# DSV1-001_V2.net
KiCad netlist of a schematic drawn in Altium Designer
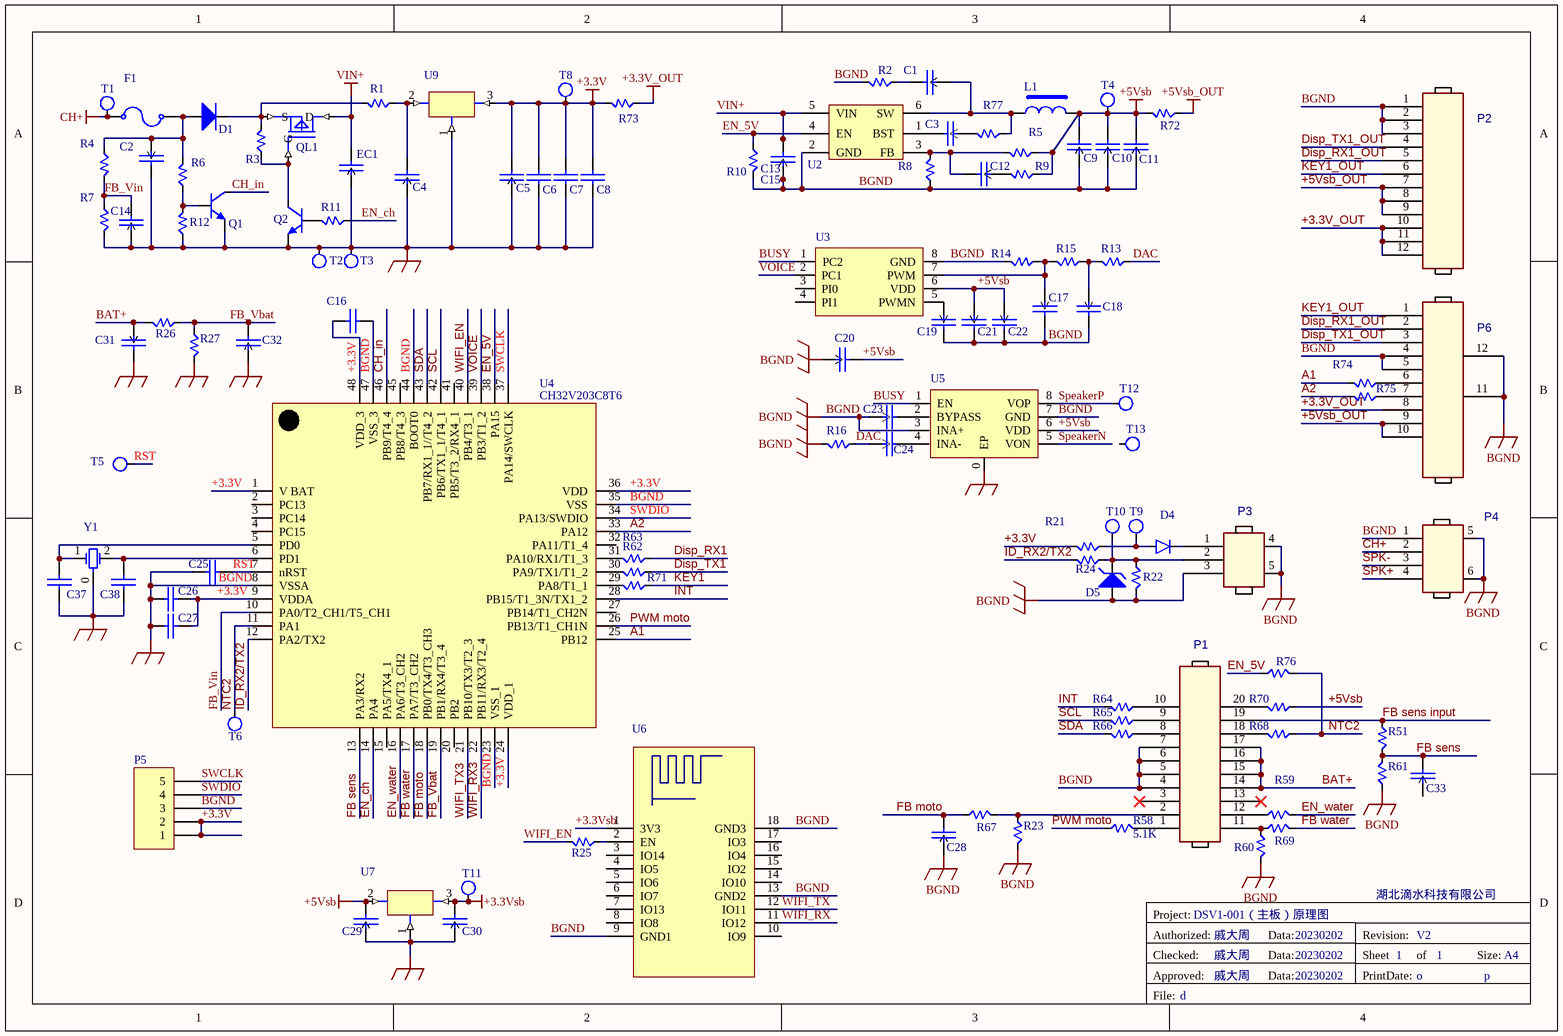
[diagram p0: DSV1-001（主板）原理图 V2.SchDoc]

(export (version "E")
  (design (tool "Eeschema 10.0.6"))
  (components
    (comp (ref "C1")
      (value "102")
      (footprint "0603C")
      (description "Capacitor")
      (libsource (lib "*") (part "CAP"))
    )
    (comp (ref "C2")
      (value "104")
      (footprint "0603C")
      (description "Capacitor")
      (libsource (lib "*") (part "CAP"))
    )
    (comp (ref "C3")
      (value "104")
      (footprint "0603C")
      (description "Capacitor")
      (libsource (lib "*") (part "CAP"))
    )
    (comp (ref "C4")
      (value "104")
      (footprint "0603C")
      (description "Capacitor")
      (libsource (lib "*") (part "CAP"))
    )
    (comp (ref "C5")
      (value "226")
      (footprint "0603C")
      (description "Capacitor")
      (libsource (lib "*") (part "CAP"))
    )
    (comp (ref "C6") (value "226") (footprint "0603c") (libsource (lib "") (part "CAP_1")))
    (comp (ref "C7") (value "103") (footprint "0603c") (libsource (lib "") (part "CAP_1")))
    (comp (ref "C8") (value "104") (footprint "0603c") (libsource (lib "") (part "CAP_1")))
    (comp (ref "C9")
      (value "226")
      (footprint "0603C")
      (description "Capacitor")
      (libsource (lib "*") (part "CAP"))
    )
    (comp (ref "C10")
      (value "226")
      (footprint "0603C")
      (description "Capacitor")
      (libsource (lib "*") (part "CAP"))
    )
    (comp (ref "C11")
      (value "104")
      (footprint "0603C")
      (description "Capacitor")
      (libsource (lib "*") (part "CAP"))
    )
    (comp (ref "C12")
      (value "101")
      (footprint "0603C")
      (description "Capacitor")
      (libsource (lib "*") (part "CAP"))
    )
    (comp (ref "C13")
      (value "104")
      (footprint "0603C")
      (description "Capacitor")
      (libsource (lib "*") (part "CAP"))
    )
    (comp (ref "C14")
      (value "104")
      (footprint "0603C")
      (description "Capacitor")
      (libsource (lib "*") (part "CAP"))
    )
    (comp (ref "C15")
      (value "104")
      (footprint "0603C")
      (description "Capacitor")
      (libsource (lib "*") (part "CAP"))
    )
    (comp (ref "C16") (value "103") (footprint "0603c") (libsource (lib "") (part "CAP_1")))
    (comp (ref "C17")
      (value "102")
      (footprint "0603C")
      (description "Capacitor")
      (libsource (lib "*") (part "CAP"))
    )
    (comp (ref "C18")
      (value "102")
      (footprint "0603C")
      (description "Capacitor")
      (libsource (lib "*") (part "CAP"))
    )
    (comp (ref "C19")
      (value "102")
      (footprint "0603C")
      (description "Capacitor")
      (libsource (lib "*") (part "CAP"))
    )
    (comp (ref "C20")
      (value "104")
      (footprint "0603C")
      (description "Capacitor")
      (libsource (lib "*") (part "CAP"))
    )
    (comp (ref "C21")
      (value "105")
      (footprint "0805C")
      (description "Capacitor")
      (libsource (lib "*") (part "CAP"))
    )
    (comp (ref "C22")
      (value "226")
      (footprint "0805C")
      (description "Capacitor")
      (libsource (lib "*") (part "CAP"))
    )
    (comp (ref "C23")
      (value "105")
      (footprint "0603C")
      (description "Capacitor")
      (libsource (lib "*") (part "CAP"))
    )
    (comp (ref "C24")
      (value "104")
      (footprint "0603C")
      (description "Capacitor")
      (libsource (lib "*") (part "CAP"))
    )
    (comp (ref "C25") (value "103") (footprint "0603c") (libsource (lib "") (part "CAP_1")))
    (comp (ref "C26") (value "104") (footprint "0603c") (libsource (lib "") (part "CAP_1")))
    (comp (ref "C27") (value "105") (footprint "0603c") (libsource (lib "") (part "CAP_1")))
    (comp (ref "C28")
      (value "104")
      (footprint "0603C")
      (description "Capacitor")
      (libsource (lib "*") (part "CAP"))
    )
    (comp (ref "C29")
      (value "NC")
      (footprint "0603c")
      (description "Capacitor")
      (libsource (lib "*") (part "CAP"))
    )
    (comp (ref "C30")
      (value "NC")
      (footprint "0603c")
      (description "Capacitor")
      (libsource (lib "*") (part "CAP"))
    )
    (comp (ref "C31")
      (value "104")
      (footprint "0603C")
      (description "Capacitor")
      (libsource (lib "*") (part "CAP"))
    )
    (comp (ref "C32")
      (value "104")
      (footprint "0603C")
      (description "Capacitor")
      (libsource (lib "*") (part "CAP"))
    )
    (comp (ref "C33")
      (value "104")
      (footprint "0603C")
      (description "Capacitor")
      (libsource (lib "*") (part "CAP"))
    )
    (comp (ref "C37") (value "12P") (footprint "0603c") (libsource (lib "") (part "CAP_1")))
    (comp (ref "C38") (value "12P") (footprint "0603c") (libsource (lib "") (part "CAP_1")))
    (comp (ref "D1")
      (value "SS54L")
      (footprint "SMB-A")
      (description "High Conductance Fast Diode")
      (libsource (lib "Miscellaneous Devices") (part "Diode 1N4448"))
    )
    (comp (ref "D4") (value "LMBR340") (footprint "SOD-123") (libsource (lib "我的元件库") (part "1N4148")))
    (comp (ref "D5")
      (value "TVS3.3V")
      (footprint "SOD-123")
      (description "Zener Diode")
      (libsource (lib "Miscellaneous Devices") (part "D Zener"))
    )
    (comp (ref "EC1")
      (value "476")
      (footprint "1210-c")
      (description "Capacitor")
      (libsource (lib "*") (part "CAP"))
    )
    (comp (ref "F1")
      (value "1200mA/24V")
      (footprint "1206-R")
      (description "Fuse")
      (libsource (lib "我的元件库") (part "FUSe-a"))
    )
    (comp (ref "L1") (value "4R7") (footprint "CLD-54") (libsource (lib "我的元件库") (part "电感")))
    (comp (ref "P1")
      (value "SGDBM-08-020P-H70")
      (footprint "SGDBM_08_020P_H40")
      (libsource (lib "*") (part "HEADER 12_1"))
    )
    (comp (ref "P2")
      (value "SGDBM-08-012P-H70")
      (footprint "SGDBM_08_012P_H40")
      (libsource (lib "*") (part "HEADER 12_0"))
    )
    (comp (ref "P3")
      (value "HEADER 3")
      (footprint "con125_03_wt_thw")
      (libsource (lib "*") (part "HEADER 3_1"))
    )
    (comp (ref "P4")
      (value "BC-60-4P300-C06")
      (footprint "BC_60_4P_C06")
      (libsource (lib "*") (part "HEADER 4_1"))
    )
    (comp (ref "P5")
      (value "~")
      (footprint "2.0-5 顶针焊盘")
      (description "Header, 5-Pin")
      (libsource (lib "Miscellaneous Connectors") (part "Header 5"))
    )
    (comp (ref "P6")
      (value "HC 0.8 10PWT")
      (footprint "HC_08_10PWT")
      (libsource (lib "*") (part "HEADER 12_2"))
    )
    (comp (ref "Q1")
      (value "MMBT2222A")
      (footprint "SOT-23-ss")
      (description "NPN General Purpose Amplifier")
      (libsource (lib "altium-import") (part "root_0__Miscellaneous Devices.IntLib"))
    )
    (comp (ref "Q2")
      (value "MMBT2222A")
      (footprint "SOT-23-ss")
      (description "NPN General Purpose Amplifier")
      (libsource (lib "altium-import") (part "root_0_mirrored__Miscellaneous Devices.IntLib"))
    )
    (comp (ref "QL1") (value "MOS-P") (footprint "SOT-23-MOS-N") (libsource (lib "Easen liu") (part "MOS-P")))
    (comp (ref "R1") (value "100R/0805") (footprint "0603R") (libsource (lib "*") (part "电阻 - R")))
    (comp (ref "R2") (value "22R") (footprint "0603R") (libsource (lib "*") (part "电阻 - R")))
    (comp (ref "R3") (value "510K") (footprint "0603r") (libsource (lib "*") (part "电阻 - R")))
    (comp (ref "R4") (value "10K") (footprint "0805R") (libsource (lib "*") (part "电阻 - R")))
    (comp (ref "R5") (value "68K") (footprint "0603R") (libsource (lib "*") (part "电阻 - R")))
    (comp (ref "R6") (value "100K") (footprint "0603R") (libsource (lib "*") (part "电阻 - R")))
    (comp (ref "R7") (value "1.6K") (footprint "0805r") (libsource (lib "*") (part "电阻 - R")))
    (comp (ref "R8") (value "9.1K") (footprint "0603R") (libsource (lib "*") (part "电阻 - R")))
    (comp (ref "R9") (value "2K") (footprint "0603R") (libsource (lib "*") (part "电阻 - R")))
    (comp (ref "R10") (value "100K") (footprint "0603R") (libsource (lib "*") (part "电阻 - R")))
    (comp (ref "R11") (value "5.1K") (footprint "0603R") (libsource (lib "*") (part "电阻 - R")))
    (comp (ref "R12") (value "10K") (footprint "0603R") (libsource (lib "*") (part "电阻 - R")))
    (comp (ref "R13") (value "10K") (footprint "0603R") (libsource (lib "*") (part "电阻 - R")))
    (comp (ref "R14") (value "470R") (footprint "0603R") (libsource (lib "*") (part "电阻 - R")))
    (comp (ref "R15") (value "4.7K") (footprint "0603R") (libsource (lib "*") (part "电阻 - R")))
    (comp (ref "R16") (value "2K") (footprint "0603R") (libsource (lib "*") (part "电阻 - R")))
    (comp (ref "R21") (value "16V/50mA") (footprint "0603r") (libsource (lib "*") (part "电阻 - R")))
    (comp (ref "R22") (value "1M") (footprint "0603R") (libsource (lib "*") (part "电阻 - R")))
    (comp (ref "R23") (value "10K") (footprint "0603R") (libsource (lib "*") (part "电阻 - R")))
    (comp (ref "R24") (value "1K") (footprint "0603r") (libsource (lib "*") (part "电阻 - R")))
    (comp (ref "R25") (value "NC") (footprint "0603r") (libsource (lib "*") (part "电阻 - R")))
    (comp (ref "R26") (value "10M") (footprint "0603r") (libsource (lib "*") (part "电阻 - R")))
    (comp (ref "R27") (value "1.6M") (footprint "0603r") (libsource (lib "*") (part "电阻 - R")))
    (comp (ref "R51") (value "5.1K") (footprint "0603R") (libsource (lib "*") (part "电阻 - R")))
    (comp (ref "R58") (value "5.1K") (footprint "0603R") (libsource (lib "*") (part "电阻 - R")))
    (comp (ref "R59") (value "5.1K") (footprint "0603R") (libsource (lib "*") (part "电阻 - R")))
    (comp (ref "R60") (value "10K") (footprint "0603R") (libsource (lib "*") (part "电阻 - R")))
    (comp (ref "R61") (value "10K") (footprint "0603R") (libsource (lib "*") (part "电阻 - R")))
    (comp (ref "R62") (value "100R") (footprint "0603R") (libsource (lib "*") (part "电阻 - R")))
    (comp (ref "R63") (value "100R") (footprint "0603R") (libsource (lib "*") (part "电阻 - R")))
    (comp (ref "R64") (value "100R") (footprint "0603R") (libsource (lib "*") (part "电阻 - R")))
    (comp (ref "R65") (value "100R") (footprint "0603R") (libsource (lib "*") (part "电阻 - R")))
    (comp (ref "R66") (value "100R") (footprint "0603R") (libsource (lib "*") (part "电阻 - R")))
    (comp (ref "R67") (value "1K") (footprint "0603R") (libsource (lib "*") (part "电阻 - R")))
    (comp (ref "R68") (value "100R") (footprint "0603R") (libsource (lib "*") (part "电阻 - R")))
    (comp (ref "R69") (value "1K") (footprint "0603R") (libsource (lib "*") (part "电阻 - R")))
    (comp (ref "R70") (value "33R") (footprint "0603R") (libsource (lib "*") (part "电阻 - R")))
    (comp (ref "R71") (value "1K") (footprint "0603R") (libsource (lib "*") (part "电阻 - R")))
    (comp (ref "R72") (value "0R") (footprint "0603R") (libsource (lib "*") (part "电阻 - R")))
    (comp (ref "R73") (value "33R") (footprint "0603R") (libsource (lib "*") (part "电阻 - R")))
    (comp (ref "R74") (value "100R") (footprint "0603R") (libsource (lib "*") (part "电阻 - R")))
    (comp (ref "R75") (value "100R") (footprint "0603R") (libsource (lib "*") (part "电阻 - R")))
    (comp (ref "R76") (value "10K") (footprint "0603R") (libsource (lib "*") (part "电阻 - R")))
    (comp (ref "R77") (value "0R") (footprint "0603R") (libsource (lib "*") (part "电阻 - R")))
    (comp (ref "T1") (value "~") (footprint "TP") (libsource (lib "*") (part "TP")))
    (comp (ref "T2") (value "~") (footprint "TP") (libsource (lib "*") (part "TP")))
    (comp (ref "T3") (value "~") (footprint "TP") (libsource (lib "*") (part "TP")))
    (comp (ref "T4") (value "~") (footprint "TP") (libsource (lib "*") (part "TP")))
    (comp (ref "T5") (value "~") (footprint "TP") (libsource (lib "*") (part "TP")))
    (comp (ref "T6") (value "~") (footprint "TP") (libsource (lib "*") (part "TP")))
    (comp (ref "T8") (value "~") (footprint "TP") (libsource (lib "*") (part "TP")))
    (comp (ref "T9") (value "~") (footprint "TP") (libsource (lib "*") (part "TP")))
    (comp (ref "T10") (value "~") (footprint "TP") (libsource (lib "*") (part "TP")))
    (comp (ref "T11") (value "~") (footprint "TP") (libsource (lib "*") (part "TP")))
    (comp (ref "T12") (value "~") (footprint "TP") (libsource (lib "*") (part "TP")))
    (comp (ref "T13") (value "~") (footprint "TP") (libsource (lib "*") (part "TP")))
    (comp (ref "U2")
      (value "JW5057S")
      (footprint "SOT23-6-T")
      (description "Header, 6-Pin")
      (libsource (lib "我的元件库") (part "Header 6"))
    )
    (comp (ref "U3")
      (value "FT61F141-RB")
      (footprint "SOP-8 xiao")
      (description "62 Pin EISA Connector")
      (libsource (lib "我的元件库") (part "IC SOT-8"))
    )
    (comp (ref "U4") (value "CH32V203C8T6") (footprint "LQFP-48") (libsource (lib "我的元件库") (part "MM32F031")))
    (comp (ref "U5")
      (value "FT61F141-RB")
      (footprint "SOP-8-0")
      (description "62 Pin EISA Connector")
      (libsource (lib "") (part "IC SOT-8_1"))
    )
    (comp (ref "U6") (value "HI3861") (footprint "ESP8266") (libsource (lib "我的元件库") (part "ESP8266")))
    (comp (ref "U7") (value "LD1117AGC33") (footprint "SOT-89") (libsource (lib "Easen liu") (part "ME6203")))
    (comp (ref "U9")
      (value "ME6239A33M3G")
      (footprint "SOT-89")
      (libsource (lib "Easen liu") (part "ME6203"))
    )
    (comp (ref "Y1") (value "8M") (footprint "3225 XTAL") (libsource (lib "我的元件库") (part "XTAL")))
  )
  (nets
    (net (code "1") (name "+3.3V") (class "Default")
      (node (ref "C16") (pin "2") (pinfunction "2_2") (pintype "passive"))
      (node (ref "C26") (pin "1") (pinfunction "1_1") (pintype "passive"))
      (node (ref "C27") (pin "1") (pinfunction "1_1") (pintype "passive"))
      (node (ref "C5") (pin "2") (pinfunction "2_2") (pintype "passive"))
      (node (ref "C6") (pin "1") (pinfunction "1_1") (pintype "passive"))
      (node (ref "C7") (pin "1") (pinfunction "1_1") (pintype "passive"))
      (node (ref "C8") (pin "1") (pinfunction "1_1") (pintype "passive"))
      (node (ref "P5") (pin "1") (pinfunction "1_1") (pintype "passive"))
      (node (ref "P5") (pin "2") (pinfunction "2_2") (pintype "passive"))
      (node (ref "R21") (pin "2") (pinfunction "2_2") (pintype "passive"))
      (node (ref "R73") (pin "2") (pinfunction "2_2") (pintype "passive"))
      (node (ref "T8") (pin "1") (pinfunction "1_1") (pintype "passive"))
      (node (ref "U4") (pin "1") (pinfunction "V_BAT_1") (pintype "passive"))
      (node (ref "U4") (pin "24") (pinfunction "VDD_1_24") (pintype "passive"))
      (node (ref "U4") (pin "36") (pinfunction "VDD_36") (pintype "passive"))
      (node (ref "U4") (pin "48") (pinfunction "VDD_3_48") (pintype "passive"))
      (node (ref "U4") (pin "9") (pinfunction "VDDA_9") (pintype "passive"))
      (node (ref "U9") (pin "3") (pinfunction "3_3") (pintype "input"))
    )
    (net (code "2") (name "+3.3V_OUT") (class "Default")
      (node (ref "P2") (pin "10") (pinfunction "10_10") (pintype "passive"))
      (node (ref "P2") (pin "11") (pinfunction "11_11") (pintype "passive"))
      (node (ref "P2") (pin "12") (pinfunction "12_12") (pintype "passive"))
      (node (ref "P6") (pin "8") (pinfunction "8_8") (pintype "passive"))
      (node (ref "R73") (pin "1") (pinfunction "1_1") (pintype "passive"))
    )
    (net (code "3") (name "+3.3Vsb") (class "Default")
      (node (ref "C30") (pin "2") (pinfunction "2_2") (pintype "passive"))
      (node (ref "T11") (pin "1") (pinfunction "1_1") (pintype "passive"))
      (node (ref "U6") (pin "1") (pinfunction "3V3_1") (pintype "open_emitter"))
      (node (ref "U7") (pin "3") (pinfunction "3_3") (pintype "input"))
    )
    (net (code "4") (name "+5Vsb") (class "Default")
      (node (ref "C10") (pin "2") (pinfunction "2_2") (pintype "passive"))
      (node (ref "C11") (pin "2") (pinfunction "2_2") (pintype "passive"))
      (node (ref "C20") (pin "2") (pinfunction "2_2") (pintype "passive"))
      (node (ref "C21") (pin "1") (pinfunction "1_1") (pintype "passive"))
      (node (ref "C22") (pin "1") (pinfunction "1_1") (pintype "passive"))
      (node (ref "C29") (pin "2") (pinfunction "2_2") (pintype "passive"))
      (node (ref "C9") (pin "2") (pinfunction "2_2") (pintype "passive"))
      (node (ref "L1") (pin "2") (pinfunction "2_2") (pintype "passive"))
      (node (ref "R5") (pin "1") (pinfunction "1_1") (pintype "passive"))
      (node (ref "R70") (pin "2") (pinfunction "2_2") (pintype "passive"))
      (node (ref "R72") (pin "2") (pinfunction "2_2") (pintype "passive"))
      (node (ref "R9") (pin "1") (pinfunction "1_1") (pintype "passive"))
      (node (ref "T4") (pin "1") (pinfunction "1_1") (pintype "passive"))
      (node (ref "U3") (pin "6") (pinfunction "VDD_6") (pintype "passive"))
      (node (ref "U5") (pin "6") (pinfunction "VDD_6") (pintype "passive"))
      (node (ref "U7") (pin "2") (pinfunction "2_2") (pintype "input"))
    )
    (net (code "5") (name "+5Vsb_OUT") (class "Default")
      (node (ref "P2") (pin "7") (pinfunction "7_7") (pintype "passive"))
      (node (ref "P2") (pin "8") (pinfunction "8_8") (pintype "passive"))
      (node (ref "P2") (pin "9") (pinfunction "9_9") (pintype "passive"))
      (node (ref "P6") (pin "10") (pinfunction "10_10") (pintype "passive"))
      (node (ref "P6") (pin "9") (pinfunction "9_9") (pintype "passive"))
      (node (ref "R72") (pin "1") (pinfunction "1_1") (pintype "passive"))
    )
    (net (code "6") (name "/A1") (class "Default")
      (node (ref "R74") (pin "2") (pinfunction "2_2") (pintype "passive"))
      (node (ref "U4") (pin "25") (pinfunction "PB12_25") (pintype "passive"))
    )
    (net (code "7") (name "/A2") (class "Default")
      (node (ref "R75") (pin "2") (pinfunction "2_2") (pintype "passive"))
      (node (ref "U4") (pin "33") (pinfunction "PA12_33") (pintype "passive"))
    )
    (net (code "8") (name "/BAT+") (class "Default")
      (node (ref "C31") (pin "1") (pinfunction "1_1") (pintype "passive"))
      (node (ref "P1") (pin "14") (pinfunction "14_14") (pintype "passive"))
      (node (ref "P1") (pin "15") (pinfunction "15_15") (pintype "passive"))
      (node (ref "P1") (pin "16") (pinfunction "16_16") (pintype "passive"))
      (node (ref "P1") (pin "17") (pinfunction "17_17") (pintype "passive"))
      (node (ref "R26") (pin "1") (pinfunction "1_1") (pintype "passive"))
    )
    (net (code "9") (name "/BUSY") (class "Default")
      (node (ref "U3") (pin "1") (pinfunction "PC2_1") (pintype "power_in"))
      (node (ref "U5") (pin "1") (pinfunction "EN_1") (pintype "power_in"))
    )
    (net (code "10") (name "/CH_in") (class "Default")
      (node (ref "Q1") (pin "3") (pinfunction "3_3") (pintype "passive"))
      (node (ref "U4") (pin "46") (pinfunction "PB9/T4_4_46") (pintype "passive"))
    )
    (net (code "11") (name "/DAC") (class "Default")
      (node (ref "C24") (pin "1") (pinfunction "1_1") (pintype "passive"))
      (node (ref "R13") (pin "2") (pinfunction "2_2") (pintype "passive"))
      (node (ref "R16") (pin "2") (pinfunction "2_2") (pintype "passive"))
    )
    (net (code "12") (name "/Disp_RX1") (class "Default")
      (node (ref "R63") (pin "2") (pinfunction "2_2") (pintype "passive"))
    )
    (net (code "13") (name "/Disp_RX1_OUT") (class "Default")
      (node (ref "P2") (pin "5") (pinfunction "5_5") (pintype "passive"))
      (node (ref "P6") (pin "2") (pinfunction "2_2") (pintype "passive"))
    )
    (net (code "14") (name "/Disp_TX1") (class "Default")
      (node (ref "R62") (pin "2") (pinfunction "2_2") (pintype "passive"))
    )
    (net (code "15") (name "/Disp_TX1_OUT") (class "Default")
      (node (ref "P2") (pin "4") (pinfunction "4_4") (pintype "passive"))
      (node (ref "P6") (pin "3") (pinfunction "3_3") (pintype "passive"))
    )
    (net (code "16") (name "/EN_5V") (class "Default")
      (node (ref "R10") (pin "1") (pinfunction "1_1") (pintype "passive"))
      (node (ref "R76") (pin "2") (pinfunction "2_2") (pintype "passive"))
      (node (ref "U2") (pin "4") (pinfunction "EN_4") (pintype "passive"))
      (node (ref "U4") (pin "38") (pinfunction "PA15_38") (pintype "passive"))
    )
    (net (code "17") (name "/EN_ch") (class "Default")
      (node (ref "R11") (pin "1") (pinfunction "1_1") (pintype "passive"))
      (node (ref "U4") (pin "14") (pinfunction "PA4_14") (pintype "passive"))
    )
    (net (code "18") (name "/EN_water") (class "Default")
      (node (ref "R59") (pin "1") (pinfunction "1_1") (pintype "passive"))
      (node (ref "U4") (pin "16") (pinfunction "PA6/T3_CH2_16") (pintype "passive"))
    )
    (net (code "19") (name "/FB moto") (class "Default")
      (node (ref "C28") (pin "2") (pinfunction "2_2") (pintype "passive"))
      (node (ref "R67") (pin "2") (pinfunction "2_2") (pintype "passive"))
      (node (ref "U4") (pin "18") (pinfunction "PB0/TX4/T3_CH3_18") (pintype "passive"))
    )
    (net (code "20") (name "/FB sens") (class "Default")
      (node (ref "C33") (pin "2") (pinfunction "2_2") (pintype "passive"))
      (node (ref "R51") (pin "1") (pinfunction "1_1") (pintype "passive"))
      (node (ref "R61") (pin "1") (pinfunction "1_1") (pintype "passive"))
      (node (ref "U4") (pin "13") (pinfunction "PA3/RX2_13") (pintype "passive"))
    )
    (net (code "21") (name "/FB sens input") (class "Default")
      (node (ref "P1") (pin "19") (pinfunction "19_19") (pintype "passive"))
      (node (ref "R51") (pin "2") (pinfunction "2_2") (pintype "passive"))
    )
    (net (code "22") (name "/FB water") (class "Default")
      (node (ref "R69") (pin "1") (pinfunction "1_1") (pintype "passive"))
      (node (ref "U4") (pin "17") (pinfunction "PA7/T3_CH2_17") (pintype "passive"))
    )
    (net (code "23") (name "/FB_Vbat") (class "Default")
      (node (ref "C32") (pin "2") (pinfunction "2_2") (pintype "passive"))
      (node (ref "R26") (pin "2") (pinfunction "2_2") (pintype "passive"))
      (node (ref "R27") (pin "2") (pinfunction "2_2") (pintype "passive"))
      (node (ref "U4") (pin "19") (pinfunction "PB1/RX4/T3_4_19") (pintype "passive"))
    )
    (net (code "24") (name "/FB_Vin") (class "Default")
      (node (ref "C14") (pin "2") (pinfunction "2_2") (pintype "passive"))
      (node (ref "R4") (pin "2") (pinfunction "2_2") (pintype "passive"))
      (node (ref "R7") (pin "2") (pinfunction "2_2") (pintype "passive"))
      (node (ref "U4") (pin "10") (pinfunction "PA0/T2_CH1/T5_CH1_10") (pintype "passive"))
    )
    (net (code "25") (name "/ID_RX2{slash}TX2") (class "Default")
      (node (ref "R24") (pin "2") (pinfunction "2_2") (pintype "passive"))
      (node (ref "U4") (pin "12") (pinfunction "PA2/TX2_12") (pintype "passive"))
    )
    (net (code "26") (name "/INT") (class "Default")
      (node (ref "R64") (pin "1") (pinfunction "1_1") (pintype "passive"))
      (node (ref "U4") (pin "28") (pinfunction "PB15/T1_3N/TX1_2_28") (pintype "passive"))
    )
    (net (code "27") (name "/KEY1") (class "Default")
      (node (ref "R71") (pin "2") (pinfunction "2_2") (pintype "passive"))
    )
    (net (code "28") (name "/KEY1_OUT") (class "Default")
      (node (ref "P2") (pin "6") (pinfunction "6_6") (pintype "passive"))
      (node (ref "P6") (pin "1") (pinfunction "1_1") (pintype "passive"))
    )
    (net (code "29") (name "/NTC2") (class "Default")
      (node (ref "R68") (pin "2") (pinfunction "2_2") (pintype "passive"))
      (node (ref "R76") (pin "1") (pinfunction "1_1") (pintype "passive"))
      (node (ref "T6") (pin "1") (pinfunction "1_1") (pintype "passive"))
      (node (ref "U4") (pin "11") (pinfunction "PA1_11") (pintype "passive"))
    )
    (net (code "30") (name "/PWM moto") (class "Default")
      (node (ref "R58") (pin "2") (pinfunction "2_2") (pintype "passive"))
      (node (ref "U4") (pin "26") (pinfunction "PB13/T1_CH1N_26") (pintype "passive"))
    )
    (net (code "31") (name "/RST") (class "Default")
      (node (ref "C25") (pin "1") (pinfunction "1_1") (pintype "passive"))
      (node (ref "T5") (pin "1") (pinfunction "1_1") (pintype "passive"))
      (node (ref "U4") (pin "7") (pinfunction "nRST_7") (pintype "passive"))
    )
    (net (code "32") (name "/SCL") (class "Default")
      (node (ref "R65") (pin "1") (pinfunction "1_1") (pintype "passive"))
      (node (ref "U4") (pin "42") (pinfunction "PB6/TX1_1/T4_1_42") (pintype "passive"))
    )
    (net (code "33") (name "/SDA") (class "Default")
      (node (ref "R66") (pin "1") (pinfunction "1_1") (pintype "passive"))
      (node (ref "U4") (pin "43") (pinfunction "PB7/RX1_1//T4_2_43") (pintype "passive"))
    )
    (net (code "34") (name "/SPK+") (class "Default")
      (node (ref "P4") (pin "4") (pinfunction "4_4") (pintype "passive"))
    )
    (net (code "35") (name "/SPK-") (class "Default")
      (node (ref "P4") (pin "3") (pinfunction "3_3") (pintype "passive"))
    )
    (net (code "36") (name "/SWCLK") (class "Default")
      (node (ref "P5") (pin "5") (pinfunction "5_5") (pintype "passive"))
      (node (ref "U4") (pin "37") (pinfunction "PA14/SWCLK_37") (pintype "passive"))
    )
    (net (code "37") (name "/SWDIO") (class "Default")
      (node (ref "P5") (pin "4") (pinfunction "4_4") (pintype "passive"))
      (node (ref "U4") (pin "34") (pinfunction "PA13/SWDIO_34") (pintype "passive"))
    )
    (net (code "38") (name "/SpeakerN") (class "Default")
      (node (ref "U5") (pin "5") (pinfunction "VON_5") (pintype "passive"))
    )
    (net (code "39") (name "/SpeakerP") (class "Default")
      (node (ref "T12") (pin "1") (pinfunction "1_1") (pintype "passive"))
      (node (ref "U5") (pin "8") (pinfunction "VOP_8") (pintype "passive"))
    )
    (net (code "40") (name "/VOICE") (class "Default")
      (node (ref "U3") (pin "2") (pinfunction "PC1_2") (pintype "power_in"))
      (node (ref "U4") (pin "39") (pinfunction "PB3/T1_2_39") (pintype "passive"))
    )
    (net (code "41") (name "/WIFI_EN") (class "Default")
      (node (ref "R25") (pin "2") (pinfunction "2_2") (pintype "passive"))
      (node (ref "U4") (pin "40") (pinfunction "PB4/T3_1_40") (pintype "passive"))
    )
    (net (code "42") (name "/WIFI_RX") (class "Default")
      (node (ref "U6") (pin "11") (pinfunction "IO12_11") (pintype "passive"))
    )
    (net (code "43") (name "/WIFI_RX3") (class "Default")
      (node (ref "U4") (pin "22") (pinfunction "PB11/RX3/T2_4_22") (pintype "passive"))
    )
    (net (code "44") (name "/WIFI_TX") (class "Default")
      (node (ref "U6") (pin "12") (pinfunction "IO11_12") (pintype "passive"))
    )
    (net (code "45") (name "/WIFI_TX3") (class "Default")
      (node (ref "U4") (pin "21") (pinfunction "PB10/TX3/T2_3_21") (pintype "passive"))
    )
    (net (code "46") (name "BGND") (class "Default")
      (node (ref "C10") (pin "1") (pinfunction "1_1") (pintype "passive"))
      (node (ref "C11") (pin "1") (pinfunction "1_1") (pintype "passive"))
      (node (ref "C13") (pin "1") (pinfunction "1_1") (pintype "passive"))
      (node (ref "C14") (pin "1") (pinfunction "1_1") (pintype "passive"))
      (node (ref "C15") (pin "1") (pinfunction "1_1") (pintype "passive"))
      (node (ref "C16") (pin "1") (pinfunction "1_1") (pintype "passive"))
      (node (ref "C17") (pin "2") (pinfunction "2_2") (pintype "passive"))
      (node (ref "C18") (pin "2") (pinfunction "2_2") (pintype "passive"))
      (node (ref "C19") (pin "2") (pinfunction "2_2") (pintype "passive"))
      (node (ref "C2") (pin "2") (pinfunction "2_2") (pintype "passive"))
      (node (ref "C20") (pin "1") (pinfunction "1_1") (pintype "passive"))
      (node (ref "C21") (pin "2") (pinfunction "2_2") (pintype "passive"))
      (node (ref "C22") (pin "2") (pinfunction "2_2") (pintype "passive"))
      (node (ref "C23") (pin "1") (pinfunction "1_1") (pintype "passive"))
      (node (ref "C25") (pin "2") (pinfunction "2_2") (pintype "passive"))
      (node (ref "C26") (pin "2") (pinfunction "2_2") (pintype "passive"))
      (node (ref "C27") (pin "2") (pinfunction "2_2") (pintype "passive"))
      (node (ref "C28") (pin "1") (pinfunction "1_1") (pintype "passive"))
      (node (ref "C29") (pin "1") (pinfunction "1_1") (pintype "passive"))
      (node (ref "C30") (pin "1") (pinfunction "1_1") (pintype "passive"))
      (node (ref "C31") (pin "2") (pinfunction "2_2") (pintype "passive"))
      (node (ref "C32") (pin "1") (pinfunction "1_1") (pintype "passive"))
      (node (ref "C37") (pin "2") (pinfunction "2_2") (pintype "passive"))
      (node (ref "C38") (pin "2") (pinfunction "2_2") (pintype "passive"))
      (node (ref "C4") (pin "1") (pinfunction "1_1") (pintype "passive"))
      (node (ref "C5") (pin "1") (pinfunction "1_1") (pintype "passive"))
      (node (ref "C6") (pin "2") (pinfunction "2_2") (pintype "passive"))
      (node (ref "C7") (pin "2") (pinfunction "2_2") (pintype "passive"))
      (node (ref "C8") (pin "2") (pinfunction "2_2") (pintype "passive"))
      (node (ref "C9") (pin "1") (pinfunction "1_1") (pintype "passive"))
      (node (ref "D5") (pin "1") (pinfunction "A_1") (pintype "passive"))
      (node (ref "EC1") (pin "1") (pinfunction "1_1") (pintype "passive"))
      (node (ref "P1") (pin "4") (pinfunction "4_4") (pintype "passive"))
      (node (ref "P1") (pin "5") (pinfunction "5_5") (pintype "passive"))
      (node (ref "P1") (pin "6") (pinfunction "6_6") (pintype "passive"))
      (node (ref "P1") (pin "7") (pinfunction "7_7") (pintype "passive"))
      (node (ref "P2") (pin "1") (pinfunction "1_1") (pintype "passive"))
      (node (ref "P2") (pin "2") (pinfunction "2_2") (pintype "passive"))
      (node (ref "P2") (pin "3") (pinfunction "3_3") (pintype "passive"))
      (node (ref "P3") (pin "3") (pinfunction "3_3") (pintype "passive"))
      (node (ref "P3") (pin "4") (pinfunction "4_4") (pintype "passive"))
      (node (ref "P3") (pin "5") (pinfunction "5_5") (pintype "passive"))
      (node (ref "P4") (pin "1") (pinfunction "1_1") (pintype "passive"))
      (node (ref "P4") (pin "5") (pinfunction "5_5") (pintype "passive"))
      (node (ref "P4") (pin "6") (pinfunction "6_6") (pintype "passive"))
      (node (ref "P5") (pin "3") (pinfunction "3_3") (pintype "passive"))
      (node (ref "P6") (pin "11") (pinfunction "11_11") (pintype "passive"))
      (node (ref "P6") (pin "12") (pinfunction "12_12") (pintype "passive"))
      (node (ref "P6") (pin "4") (pinfunction "4_4") (pintype "passive"))
      (node (ref "P6") (pin "5") (pinfunction "5_5") (pintype "passive"))
      (node (ref "Q1") (pin "2") (pinfunction "2_2") (pintype "passive"))
      (node (ref "Q2") (pin "2") (pinfunction "2_2") (pintype "passive"))
      (node (ref "R10") (pin "2") (pinfunction "2_2") (pintype "passive"))
      (node (ref "R12") (pin "1") (pinfunction "1_1") (pintype "passive"))
      (node (ref "R14") (pin "1") (pinfunction "1_1") (pintype "passive"))
      (node (ref "R16") (pin "1") (pinfunction "1_1") (pintype "passive"))
      (node (ref "R2") (pin "2") (pinfunction "2_2") (pintype "passive"))
      (node (ref "R22") (pin "1") (pinfunction "1_1") (pintype "passive"))
      (node (ref "R23") (pin "1") (pinfunction "1_1") (pintype "passive"))
      (node (ref "R27") (pin "1") (pinfunction "1_1") (pintype "passive"))
      (node (ref "R60") (pin "1") (pinfunction "1_1") (pintype "passive"))
      (node (ref "R61") (pin "2") (pinfunction "2_2") (pintype "passive"))
      (node (ref "R7") (pin "1") (pinfunction "1_1") (pintype "passive"))
      (node (ref "R8") (pin "1") (pinfunction "1_1") (pintype "passive"))
      (node (ref "T2") (pin "1") (pinfunction "1_1") (pintype "passive"))
      (node (ref "T3") (pin "1") (pinfunction "1_1") (pintype "passive"))
      (node (ref "U2") (pin "2") (pinfunction "GND_2") (pintype "passive"))
      (node (ref "U3") (pin "8") (pinfunction "GND_8") (pintype "passive"))
      (node (ref "U4") (pin "23") (pinfunction "VSS_1_23") (pintype "passive"))
      (node (ref "U4") (pin "35") (pinfunction "VSS_35") (pintype "passive"))
      (node (ref "U4") (pin "44") (pinfunction "BOOT0_44") (pintype "passive"))
      (node (ref "U4") (pin "47") (pinfunction "VSS_3_47") (pintype "passive"))
      (node (ref "U4") (pin "8") (pinfunction "VSSA_8") (pintype "passive"))
      (node (ref "U5") (pin "0") (pinfunction "EP_0") (pintype "passive"))
      (node (ref "U5") (pin "3") (pinfunction "INA+_3") (pintype "power_in"))
      (node (ref "U5") (pin "7") (pinfunction "GND_7") (pintype "passive"))
      (node (ref "U6") (pin "13") (pinfunction "GND2_13") (pintype "passive"))
      (node (ref "U6") (pin "18") (pinfunction "GND3_18") (pintype "passive"))
      (node (ref "U6") (pin "9") (pinfunction "GND1_9") (pintype "open_emitter"))
      (node (ref "U7") (pin "1") (pinfunction "1_1") (pintype "input"))
      (node (ref "U9") (pin "1") (pinfunction "1_1") (pintype "input"))
      (node (ref "Y1") (pin "0") (pinfunction "GND_0") (pintype "passive"))
    )
    (net (code "47") (name "CH+") (class "Default")
      (node (ref "F1") (pin "1") (pinfunction "1_1") (pintype "passive"))
      (node (ref "P4") (pin "2") (pinfunction "2_2") (pintype "passive"))
      (node (ref "T1") (pin "1") (pinfunction "1_1") (pintype "passive"))
    )
    (net (code "48") (name "Net-(C1-Pad2)") (class "Default")
      (node (ref "C1") (pin "2") (pinfunction "2_2") (pintype "passive"))
      (node (ref "R2") (pin "1") (pinfunction "1_1") (pintype "passive"))
    )
    (net (code "49") (name "Net-(C3-Pad1)") (class "Default")
      (node (ref "C3") (pin "1") (pinfunction "1_1") (pintype "passive"))
      (node (ref "R77") (pin "2") (pinfunction "2_2") (pintype "passive"))
    )
    (net (code "50") (name "Net-(C4-Pad2)") (class "Default")
      (node (ref "C4") (pin "2") (pinfunction "2_2") (pintype "passive"))
      (node (ref "R1") (pin "1") (pinfunction "1_1") (pintype "passive"))
      (node (ref "U9") (pin "2") (pinfunction "2_2") (pintype "input"))
    )
    (net (code "51") (name "Net-(C12-Pad1)") (class "Default")
      (node (ref "C12") (pin "1") (pinfunction "1_1") (pintype "passive"))
      (node (ref "R9") (pin "2") (pinfunction "2_2") (pintype "passive"))
    )
    (net (code "52") (name "Net-(C18-Pad1)") (class "Default")
      (node (ref "C18") (pin "1") (pinfunction "1_1") (pintype "passive"))
      (node (ref "R13") (pin "1") (pinfunction "1_1") (pintype "passive"))
      (node (ref "R15") (pin "2") (pinfunction "2_2") (pintype "passive"))
    )
    (net (code "53") (name "Net-(D1-A)") (class "Default")
      (node (ref "C2") (pin "1") (pinfunction "1_1") (pintype "passive"))
      (node (ref "D1") (pin "1") (pinfunction "A_1") (pintype "passive"))
      (node (ref "F1") (pin "2") (pinfunction "2_2") (pintype "passive"))
      (node (ref "R4") (pin "1") (pinfunction "1_1") (pintype "passive"))
      (node (ref "R6") (pin "2") (pinfunction "2_2") (pintype "passive"))
    )
    (net (code "54") (name "Net-(D1-K)") (class "Default")
      (node (ref "D1") (pin "2") (pinfunction "K_2") (pintype "passive"))
      (node (ref "QL1") (pin "S") (pinfunction "S_S") (pintype "input"))
      (node (ref "R1") (pin "2") (pinfunction "2_2") (pintype "passive"))
      (node (ref "R3") (pin "2") (pinfunction "2_2") (pintype "passive"))
    )
    (net (code "55") (name "Net-(D4-Pad1)") (class "Default")
      (node (ref "D4") (pin "1") (pinfunction "1_1") (pintype "passive"))
      (node (ref "R21") (pin "1") (pinfunction "1_1") (pintype "passive"))
      (node (ref "T9") (pin "1") (pinfunction "1_1") (pintype "passive"))
    )
    (net (code "56") (name "Net-(D4-Pad2)") (class "Default")
      (node (ref "D4") (pin "2") (pinfunction "2_2") (pintype "passive"))
      (node (ref "P3") (pin "1") (pinfunction "1_1") (pintype "passive"))
    )
    (net (code "57") (name "Net-(D5-K)") (class "Default")
      (node (ref "D5") (pin "2") (pinfunction "K_2") (pintype "passive"))
      (node (ref "P3") (pin "2") (pinfunction "2_2") (pintype "passive"))
      (node (ref "R22") (pin "2") (pinfunction "2_2") (pintype "passive"))
      (node (ref "R24") (pin "1") (pinfunction "1_1") (pintype "passive"))
      (node (ref "T10") (pin "1") (pinfunction "1_1") (pintype "passive"))
    )
    (net (code "58") (name "Net-(P1-Pad1)") (class "Default")
      (node (ref "P1") (pin "1") (pinfunction "1_1") (pintype "passive"))
      (node (ref "R58") (pin "1") (pinfunction "1_1") (pintype "passive"))
    )
    (net (code "59") (name "Net-(P1-Pad2)") (class "Default")
      (node (ref "P1") (pin "2") (pinfunction "2_2") (pintype "passive"))
      (node (ref "R23") (pin "2") (pinfunction "2_2") (pintype "passive"))
      (node (ref "R67") (pin "1") (pinfunction "1_1") (pintype "passive"))
    )
    (net (code "60") (name "Net-(P1-Pad8)") (class "Default")
      (node (ref "P1") (pin "8") (pinfunction "8_8") (pintype "passive"))
      (node (ref "R66") (pin "2") (pinfunction "2_2") (pintype "passive"))
    )
    (net (code "61") (name "Net-(P1-Pad9)") (class "Default")
      (node (ref "P1") (pin "9") (pinfunction "9_9") (pintype "passive"))
      (node (ref "R65") (pin "2") (pinfunction "2_2") (pintype "passive"))
    )
    (net (code "62") (name "Net-(P1-Pad10)") (class "Default")
      (node (ref "P1") (pin "10") (pinfunction "10_10") (pintype "passive"))
      (node (ref "R64") (pin "2") (pinfunction "2_2") (pintype "passive"))
    )
    (net (code "63") (name "Net-(P1-Pad11)") (class "Default")
      (node (ref "P1") (pin "11") (pinfunction "11_11") (pintype "passive"))
      (node (ref "R60") (pin "2") (pinfunction "2_2") (pintype "passive"))
      (node (ref "R69") (pin "2") (pinfunction "2_2") (pintype "passive"))
    )
    (net (code "64") (name "Net-(P1-Pad12)") (class "Default")
      (node (ref "P1") (pin "12") (pinfunction "12_12") (pintype "passive"))
      (node (ref "R59") (pin "2") (pinfunction "2_2") (pintype "passive"))
    )
    (net (code "65") (name "Net-(P1-Pad18)") (class "Default")
      (node (ref "P1") (pin "18") (pinfunction "18_18") (pintype "passive"))
      (node (ref "R68") (pin "1") (pinfunction "1_1") (pintype "passive"))
    )
    (net (code "66") (name "Net-(P1-Pad20)") (class "Default")
      (node (ref "P1") (pin "20") (pinfunction "20_20") (pintype "passive"))
      (node (ref "R70") (pin "1") (pinfunction "1_1") (pintype "passive"))
    )
    (net (code "67") (name "Net-(P6-Pad6)") (class "Default")
      (node (ref "P6") (pin "6") (pinfunction "6_6") (pintype "passive"))
      (node (ref "R74") (pin "1") (pinfunction "1_1") (pintype "passive"))
    )
    (net (code "68") (name "Net-(P6-Pad7)") (class "Default")
      (node (ref "P6") (pin "7") (pinfunction "7_7") (pintype "passive"))
      (node (ref "R75") (pin "1") (pinfunction "1_1") (pintype "passive"))
    )
    (net (code "69") (name "Net-(Q1-Pad1)") (class "Default")
      (node (ref "Q1") (pin "1") (pinfunction "1_1") (pintype "passive"))
      (node (ref "R12") (pin "2") (pinfunction "2_2") (pintype "passive"))
      (node (ref "R6") (pin "1") (pinfunction "1_1") (pintype "passive"))
    )
    (net (code "70") (name "Net-(Q2-Pad1)") (class "Default")
      (node (ref "Q2") (pin "1") (pinfunction "1_1") (pintype "passive"))
      (node (ref "R11") (pin "2") (pinfunction "2_2") (pintype "passive"))
    )
    (net (code "71") (name "Net-(Q2-Pad3)") (class "Default")
      (node (ref "Q2") (pin "3") (pinfunction "3_3") (pintype "passive"))
      (node (ref "QL1") (pin "G") (pinfunction "G_G") (pintype "input"))
      (node (ref "R3") (pin "1") (pinfunction "1_1") (pintype "passive"))
    )
    (net (code "72") (name "Net-(U2-BST)") (class "Default")
      (node (ref "C3") (pin "2") (pinfunction "2_2") (pintype "passive"))
      (node (ref "U2") (pin "1") (pinfunction "BST_1") (pintype "passive"))
    )
    (net (code "73") (name "Net-(U2-FB)") (class "Default")
      (node (ref "C12") (pin "2") (pinfunction "2_2") (pintype "passive"))
      (node (ref "R5") (pin "2") (pinfunction "2_2") (pintype "passive"))
      (node (ref "R8") (pin "2") (pinfunction "2_2") (pintype "passive"))
      (node (ref "U2") (pin "3") (pinfunction "FB_3") (pintype "passive"))
    )
    (net (code "74") (name "Net-(U2-SW)") (class "Default")
      (node (ref "C1") (pin "1") (pinfunction "1_1") (pintype "passive"))
      (node (ref "L1") (pin "1") (pinfunction "1_1") (pintype "passive"))
      (node (ref "R77") (pin "1") (pinfunction "1_1") (pintype "passive"))
      (node (ref "U2") (pin "6") (pinfunction "SW_6") (pintype "passive"))
    )
    (net (code "75") (name "Net-(U3-PWM)") (class "Default")
      (node (ref "C17") (pin "1") (pinfunction "1_1") (pintype "passive"))
      (node (ref "R14") (pin "2") (pinfunction "2_2") (pintype "passive"))
      (node (ref "R15") (pin "1") (pinfunction "1_1") (pintype "passive"))
      (node (ref "U3") (pin "7") (pinfunction "PWM_7") (pintype "passive"))
    )
    (net (code "76") (name "Net-(U3-PWMN)") (class "Default")
      (node (ref "C19") (pin "1") (pinfunction "1_1") (pintype "passive"))
      (node (ref "U3") (pin "5") (pinfunction "PWMN_5") (pintype "passive"))
    )
    (net (code "77") (name "Net-(U4-PA8{slash}T1_1)") (class "Default")
      (node (ref "R71") (pin "1") (pinfunction "1_1") (pintype "passive"))
      (node (ref "U4") (pin "29") (pinfunction "PA8/T1_1_29") (pintype "passive"))
    )
    (net (code "78") (name "Net-(U4-PA9{slash}TX1{slash}T1_2)") (class "Default")
      (node (ref "R62") (pin "1") (pinfunction "1_1") (pintype "passive"))
      (node (ref "U4") (pin "30") (pinfunction "PA9/TX1/T1_2_30") (pintype "passive"))
    )
    (net (code "79") (name "Net-(U4-PA10{slash}RX1{slash}T1_3)") (class "Default")
      (node (ref "R63") (pin "1") (pinfunction "1_1") (pintype "passive"))
      (node (ref "U4") (pin "31") (pinfunction "PA10/RX1/T1_3_31") (pintype "passive"))
    )
    (net (code "80") (name "Net-(U4-PD0)") (class "Default")
      (node (ref "C37") (pin "1") (pinfunction "1_1") (pintype "passive"))
      (node (ref "U4") (pin "5") (pinfunction "PD0_5") (pintype "passive"))
      (node (ref "Y1") (pin "1") (pinfunction "OSC1_1") (pintype "passive"))
    )
    (net (code "81") (name "Net-(U4-PD1)") (class "Default")
      (node (ref "C38") (pin "1") (pinfunction "1_1") (pintype "passive"))
      (node (ref "U4") (pin "6") (pinfunction "PD1_6") (pintype "passive"))
      (node (ref "Y1") (pin "2") (pinfunction "OSC2_2") (pintype "passive"))
    )
    (net (code "82") (name "Net-(U5-BYPASS)") (class "Default")
      (node (ref "C23") (pin "2") (pinfunction "2_2") (pintype "passive"))
      (node (ref "U5") (pin "2") (pinfunction "BYPASS_2") (pintype "power_in"))
    )
    (net (code "83") (name "Net-(U5-INA-)") (class "Default")
      (node (ref "C24") (pin "2") (pinfunction "2_2") (pintype "passive"))
      (node (ref "U5") (pin "4") (pinfunction "INA-_4") (pintype "passive"))
    )
    (net (code "84") (name "Net-(U6-EN)") (class "Default")
      (node (ref "R25") (pin "1") (pinfunction "1_1") (pintype "passive"))
      (node (ref "U6") (pin "2") (pinfunction "EN_2") (pintype "passive"))
    )
    (net (code "85") (name "VIN+") (class "Default")
      (node (ref "C13") (pin "2") (pinfunction "2_2") (pintype "passive"))
      (node (ref "C15") (pin "2") (pinfunction "2_2") (pintype "passive"))
      (node (ref "EC1") (pin "2") (pinfunction "2_2") (pintype "passive"))
      (node (ref "QL1") (pin "D") (pinfunction "D_D") (pintype "input"))
      (node (ref "U2") (pin "5") (pinfunction "VIN_5") (pintype "passive"))
    )
    (net (code "86") (name "unconnected-(C33-Pad1)") (class "Default")
      (node (ref "C33") (pin "1") (pinfunction "1_1") (pintype "passive"))
    )
    (net (code "87") (name "unconnected-(P1-Pad3)") (class "Default")
      (node (ref "P1") (pin "3") (pinfunction "3_3") (pintype "passive+no_connect"))
    )
    (net (code "88") (name "unconnected-(P1-Pad13)") (class "Default")
      (node (ref "P1") (pin "13") (pinfunction "13_13") (pintype "passive+no_connect"))
    )
    (net (code "89") (name "unconnected-(T13-Pad1)") (class "Default")
      (node (ref "T13") (pin "1") (pinfunction "1_1") (pintype "passive"))
    )
    (net (code "90") (name "unconnected-(U3-PI0-Pad3)") (class "Default")
      (node (ref "U3") (pin "3") (pinfunction "PI0_3") (pintype "power_in"))
    )
    (net (code "91") (name "unconnected-(U3-PI1-Pad4)") (class "Default")
      (node (ref "U3") (pin "4") (pinfunction "PI1_4") (pintype "passive"))
    )
    (net (code "92") (name "unconnected-(U4-PA5{slash}TX4_1-Pad15)") (class "Default")
      (node (ref "U4") (pin "15") (pinfunction "PA5/TX4_1_15") (pintype "passive"))
    )
    (net (code "93") (name "unconnected-(U4-PA11{slash}T1_4-Pad32)") (class "Default")
      (node (ref "U4") (pin "32") (pinfunction "PA11/T1_4_32") (pintype "passive"))
    )
    (net (code "94") (name "unconnected-(U4-PB2-Pad20)") (class "Default")
      (node (ref "U4") (pin "20") (pinfunction "PB2_20") (pintype "passive"))
    )
    (net (code "95") (name "unconnected-(U4-PB5{slash}T3_2{slash}RX4_1-Pad41)") (class "Default")
      (node (ref "U4") (pin "41") (pinfunction "PB5/T3_2/RX4_1_41") (pintype "passive"))
    )
    (net (code "96") (name "unconnected-(U4-PB8{slash}T4_3-Pad45)") (class "Default")
      (node (ref "U4") (pin "45") (pinfunction "PB8/T4_3_45") (pintype "passive"))
    )
    (net (code "97") (name "unconnected-(U4-PB14{slash}T1_CH2N-Pad27)") (class "Default")
      (node (ref "U4") (pin "27") (pinfunction "PB14/T1_CH2N_27") (pintype "passive"))
    )
    (net (code "98") (name "unconnected-(U4-PC13-Pad2)") (class "Default")
      (node (ref "U4") (pin "2") (pinfunction "PC13_2") (pintype "passive"))
    )
    (net (code "99") (name "unconnected-(U4-PC14-Pad3)") (class "Default")
      (node (ref "U4") (pin "3") (pinfunction "PC14_3") (pintype "passive"))
    )
    (net (code "100") (name "unconnected-(U4-PC15-Pad4)") (class "Default")
      (node (ref "U4") (pin "4") (pinfunction "PC15_4") (pintype "passive"))
    )
    (net (code "101") (name "unconnected-(U6-IO2-Pad15)") (class "Default")
      (node (ref "U6") (pin "15") (pinfunction "IO2_15") (pintype "passive"))
    )
    (net (code "102") (name "unconnected-(U6-IO3-Pad17)") (class "Default")
      (node (ref "U6") (pin "17") (pinfunction "IO3_17") (pintype "passive"))
    )
    (net (code "103") (name "unconnected-(U6-IO4-Pad16)") (class "Default")
      (node (ref "U6") (pin "16") (pinfunction "IO4_16") (pintype "passive"))
    )
    (net (code "104") (name "unconnected-(U6-IO5-Pad4)") (class "Default")
      (node (ref "U6") (pin "4") (pinfunction "IO5_4") (pintype "passive"))
    )
    (net (code "105") (name "unconnected-(U6-IO6-Pad5)") (class "Default")
      (node (ref "U6") (pin "5") (pinfunction "IO6_5") (pintype "passive"))
    )
    (net (code "106") (name "unconnected-(U6-IO7-Pad6)") (class "Default")
      (node (ref "U6") (pin "6") (pinfunction "IO7_6") (pintype "passive"))
    )
    (net (code "107") (name "unconnected-(U6-IO8-Pad8)") (class "Default")
      (node (ref "U6") (pin "8") (pinfunction "IO8_8") (pintype "passive"))
    )
    (net (code "108") (name "unconnected-(U6-IO9-Pad10)") (class "Default")
      (node (ref "U6") (pin "10") (pinfunction "IO9_10") (pintype "passive"))
    )
    (net (code "109") (name "unconnected-(U6-IO10-Pad14)") (class "Default")
      (node (ref "U6") (pin "14") (pinfunction "IO10_14") (pintype "passive"))
    )
    (net (code "110") (name "unconnected-(U6-IO13-Pad7)") (class "Default")
      (node (ref "U6") (pin "7") (pinfunction "IO13_7") (pintype "passive"))
    )
    (net (code "111") (name "unconnected-(U6-IO14-Pad3)") (class "Default")
      (node (ref "U6") (pin "3") (pinfunction "IO14_3") (pintype "passive"))
    )
  )
)
